# RPM_meter.net
KiCad netlist of a schematic drawn in EAGLE
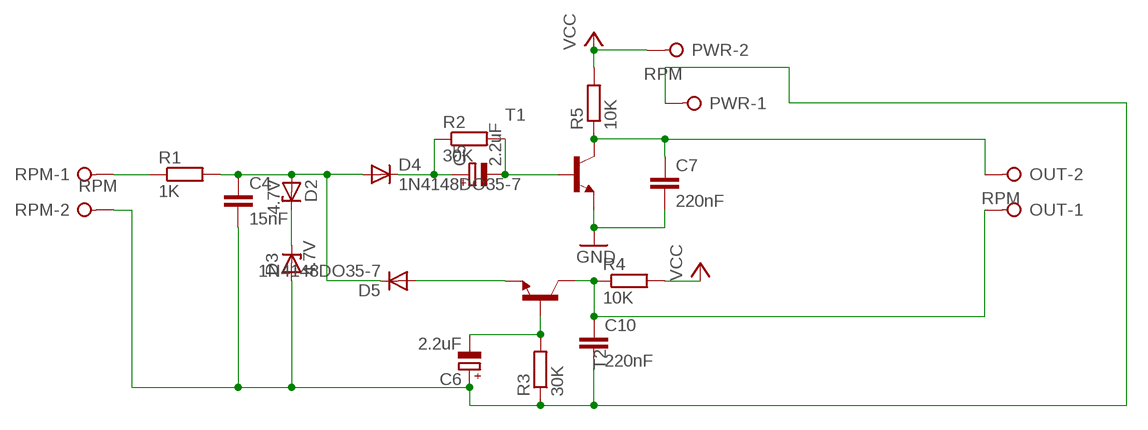
[diagram p0: schematic, sheet 1]

(export (version "E")
  (design (tool "Eeschema 10.0.6"))
  (components
    (comp (ref "C4")
      (value "15nF")
      (footprint "eagle-import:C025-024X044")
      (libsource (lib "eagle-import") (part "C-EU025-024X044"))
    )
    (comp (ref "C5")
      (value "2.2uF")
      (footprint "eagle-import:E1,8-4")
      (libsource (lib "eagle-import") (part "CPOL-EUE1.8-4"))
    )
    (comp (ref "C6")
      (value "2.2uF")
      (footprint "eagle-import:E1,8-4")
      (libsource (lib "eagle-import") (part "CPOL-EUE1.8-4"))
    )
    (comp (ref "C7")
      (value "220nF")
      (footprint "eagle-import:C025-024X044")
      (libsource (lib "eagle-import") (part "C-EU025-024X044"))
    )
    (comp (ref "C10")
      (value "220nF")
      (footprint "eagle-import:C025-024X044")
      (libsource (lib "eagle-import") (part "C-EU025-024X044"))
    )
    (comp (ref "D2")
      (value "4.7V")
      (footprint "eagle-import:ZDIO-10")
      (libsource (lib "eagle-import") (part "ZENER-DIODEZD-10"))
    )
    (comp (ref "D3")
      (value "4.7V")
      (footprint "eagle-import:ZDIO-10")
      (libsource (lib "eagle-import") (part "ZENER-DIODEZD-10"))
    )
    (comp (ref "D4")
      (value "1N4148DO35-7")
      (footprint "eagle-import:DO35-7")
      (libsource (lib "eagle-import") (part "1N4148DO35-7"))
    )
    (comp (ref "D5")
      (value "1N4148DO35-7")
      (footprint "eagle-import:DO35-7")
      (libsource (lib "eagle-import") (part "1N4148DO35-7"))
    )
    (comp (ref "OUT")
      (value "RPM")
      (footprint "eagle-import:W237-132")
      (libsource (lib "eagle-import") (part "W237-02P"))
    )
    (comp (ref "PWR")
      (value "RPM")
      (footprint "eagle-import:W237-132")
      (libsource (lib "eagle-import") (part "W237-02P"))
    )
    (comp (ref "R1")
      (value "1K")
      (footprint "eagle-import:0207_7")
      (libsource (lib "eagle-import") (part "R-EU_0207/7"))
    )
    (comp (ref "R2")
      (value "30K")
      (footprint "eagle-import:0207_7")
      (libsource (lib "eagle-import") (part "R-EU_0207/7"))
    )
    (comp (ref "R3")
      (value "30K")
      (footprint "eagle-import:0207_7")
      (libsource (lib "eagle-import") (part "R-EU_0207/7"))
    )
    (comp (ref "R4")
      (value "10K")
      (footprint "eagle-import:0207_7")
      (libsource (lib "eagle-import") (part "R-EU_0207/7"))
    )
    (comp (ref "R5")
      (value "10K")
      (footprint "eagle-import:0207_7")
      (libsource (lib "eagle-import") (part "R-EU_0207/7"))
    )
    (comp (ref "RPM")
      (value "RPM")
      (footprint "eagle-import:W237-132")
      (libsource (lib "eagle-import") (part "W237-02P"))
    )
    (comp (ref "T1")
      (value "2N2222-NPN-TO92-EBC")
      (footprint "eagle-import:TO92-EBC")
      (libsource (lib "eagle-import") (part "-NPN-TO92-EBC2N2222"))
    )
    (comp (ref "T2")
      (value "2N2222-NPN-TO92-EBC")
      (footprint "eagle-import:TO92-EBC")
      (libsource (lib "eagle-import") (part "-NPN-TO92-EBC2N2222"))
    )
  )
  (nets
    (net (code "1") (name "GND") (class "Default")
      (node (ref "C7") (pin "2") (pinfunction "2_2") (pintype "passive"))
      (node (ref "T1") (pin "E") (pinfunction "E_E") (pintype "passive"))
    )
    (net (code "2") (name "Net-(C4-Pad1)") (class "Default")
      (node (ref "C4") (pin "1") (pinfunction "1_1") (pintype "passive"))
      (node (ref "D2") (pin "A") (pinfunction "A_A") (pintype "passive"))
      (node (ref "D4") (pin "A") (pinfunction "A_A") (pintype "passive"))
      (node (ref "D5") (pin "C") (pinfunction "C_C") (pintype "passive"))
      (node (ref "R1") (pin "2") (pinfunction "2_2") (pintype "passive"))
    )
    (net (code "3") (name "Net-(C5-Pad+)") (class "Default")
      (node (ref "C5") (pin "+") (pinfunction "+_+") (pintype "passive"))
      (node (ref "D4") (pin "C") (pinfunction "C_C") (pintype "passive"))
      (node (ref "R2") (pin "1") (pinfunction "1_1") (pintype "passive"))
    )
    (net (code "4") (name "Net-(C5-Pad-)") (class "Default")
      (node (ref "C5") (pin "-") (pinfunction "-_-") (pintype "passive"))
      (node (ref "R2") (pin "2") (pinfunction "2_2") (pintype "passive"))
      (node (ref "T1") (pin "B") (pinfunction "B_B") (pintype "passive"))
    )
    (net (code "5") (name "Net-(C6-Pad-)") (class "Default")
      (node (ref "C6") (pin "-") (pinfunction "-_-") (pintype "passive"))
      (node (ref "R3") (pin "2") (pinfunction "2_2") (pintype "passive"))
      (node (ref "T2") (pin "B") (pinfunction "B_B") (pintype "passive"))
    )
    (net (code "6") (name "Net-(D2-PadC)") (class "Default")
      (node (ref "D2") (pin "C") (pinfunction "C_C") (pintype "passive"))
      (node (ref "D3") (pin "C") (pinfunction "C_C") (pintype "passive"))
    )
    (net (code "7") (name "Net-(D5-PadA)") (class "Default")
      (node (ref "D5") (pin "A") (pinfunction "A_A") (pintype "passive"))
      (node (ref "T2") (pin "E") (pinfunction "E_E") (pintype "passive"))
    )
    (net (code "8") (name "Net-(OUTA-KL)") (class "Default")
      (node (ref "C10") (pin "1") (pinfunction "1_1") (pintype "passive"))
      (node (ref "OUT") (pin "1") (pinfunction "KL_1") (pintype "passive"))
      (node (ref "R4") (pin "1") (pinfunction "1_1") (pintype "passive"))
      (node (ref "T2") (pin "C") (pinfunction "C_C") (pintype "passive"))
    )
    (net (code "9") (name "Net-(OUTB-KL)") (class "Default")
      (node (ref "C7") (pin "1") (pinfunction "1_1") (pintype "passive"))
      (node (ref "OUT") (pin "2") (pinfunction "KL_2") (pintype "passive"))
      (node (ref "R5") (pin "1") (pinfunction "1_1") (pintype "passive"))
      (node (ref "T1") (pin "C") (pinfunction "C_C") (pintype "passive"))
    )
    (net (code "10") (name "Net-(PWRA-KL)") (class "Default")
      (node (ref "C10") (pin "2") (pinfunction "2_2") (pintype "passive"))
      (node (ref "C4") (pin "2") (pinfunction "2_2") (pintype "passive"))
      (node (ref "C6") (pin "+") (pinfunction "+_+") (pintype "passive"))
      (node (ref "D3") (pin "A") (pinfunction "A_A") (pintype "passive"))
      (node (ref "PWR") (pin "1") (pinfunction "KL_1") (pintype "passive"))
      (node (ref "R3") (pin "1") (pinfunction "1_1") (pintype "passive"))
      (node (ref "RPM") (pin "2") (pinfunction "KL_2") (pintype "passive"))
    )
    (net (code "11") (name "Net-(RPMA-KL)") (class "Default")
      (node (ref "R1") (pin "1") (pinfunction "1_1") (pintype "passive"))
      (node (ref "RPM") (pin "1") (pinfunction "KL_1") (pintype "passive"))
    )
    (net (code "12") (name "VCC") (class "Default")
      (node (ref "PWR") (pin "2") (pinfunction "KL_2") (pintype "passive"))
      (node (ref "R4") (pin "2") (pinfunction "2_2") (pintype "passive"))
      (node (ref "R5") (pin "2") (pinfunction "2_2") (pintype "passive"))
    )
  )
)
